# ATX_Power_Breakout_v1p5.net
KiCad netlist of a schematic drawn in EAGLE
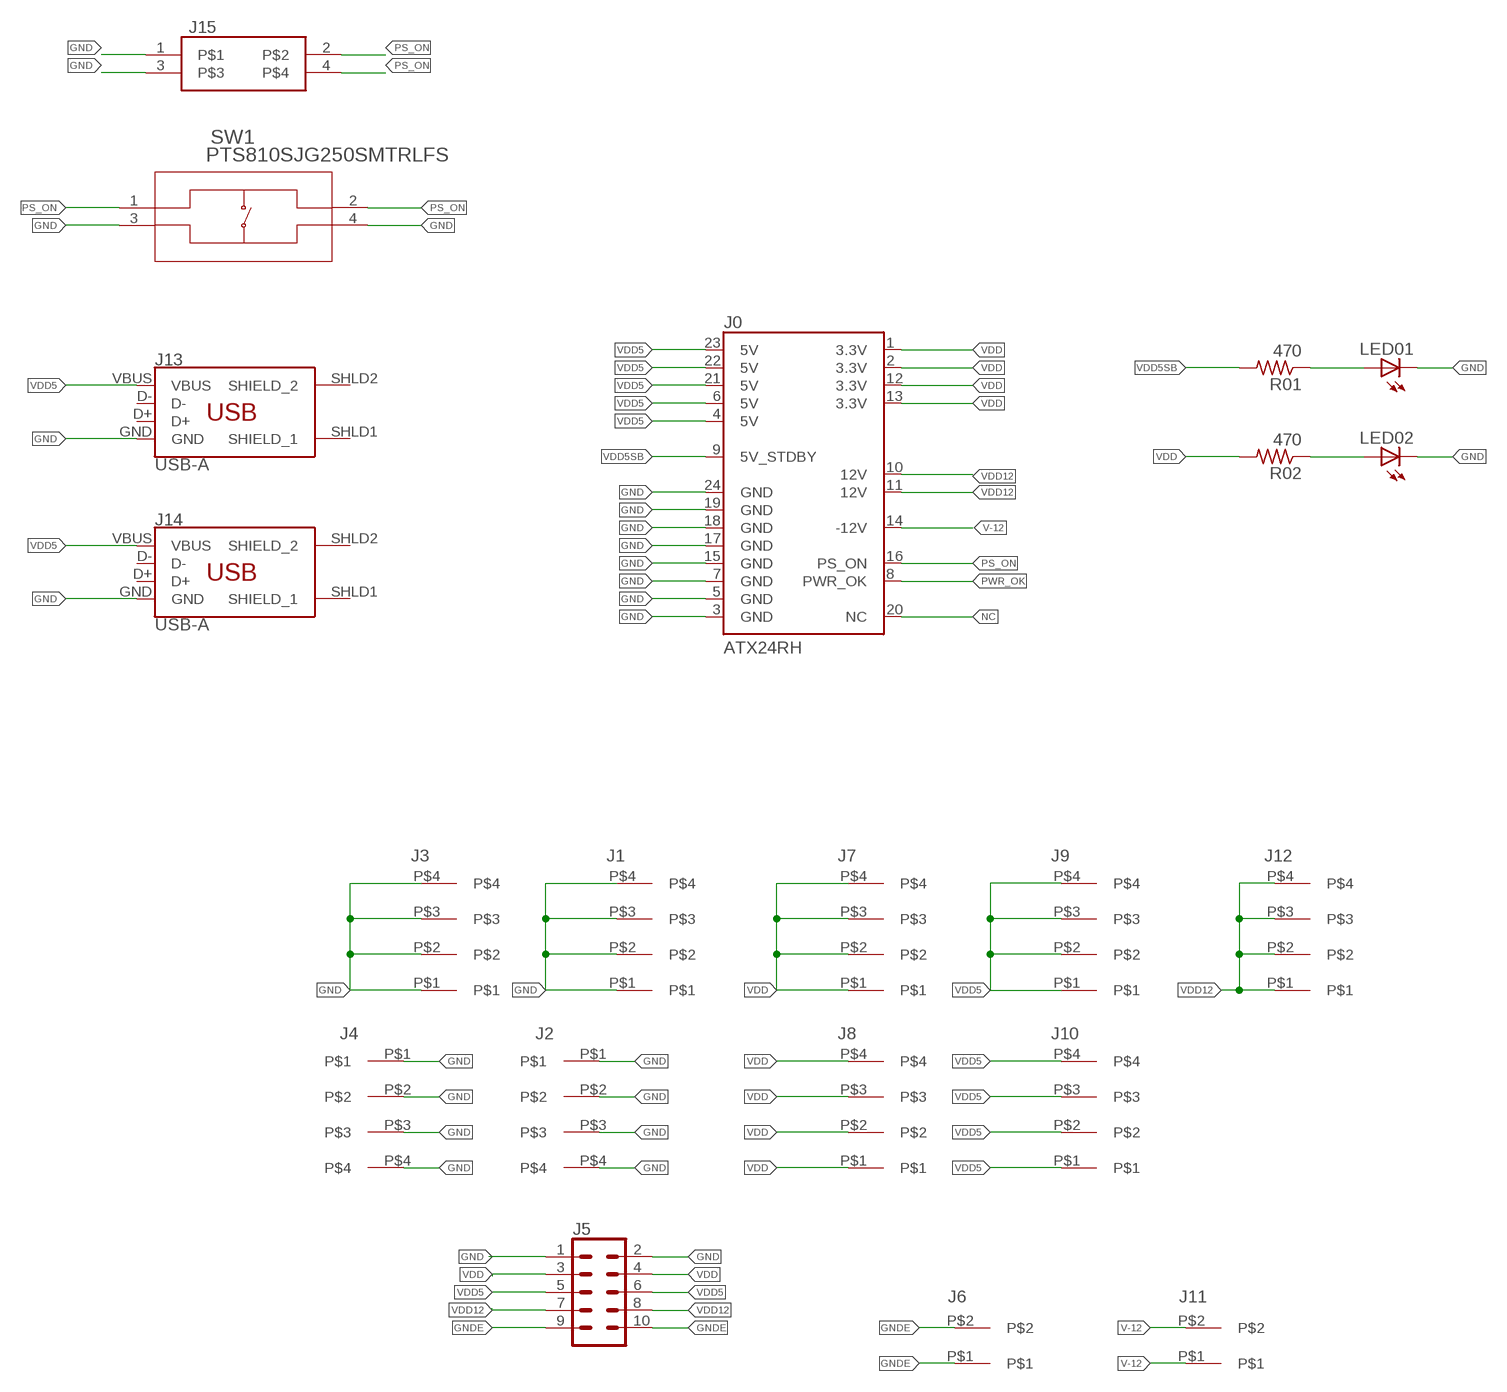
[diagram p0: schematic, sheet 1]

(export (version "E")
  (design (tool "Eeschema 10.0.6"))
  (components
    (comp (ref "J0")
      (value "ATX24RH")
      (footprint "eagle-import:ATX24_RIGHT_ANGLE")
      (libsource (lib "eagle-import") (part "ATX24RH"))
    )
    (comp (ref "J1")
      (value "3.81MM_1_X_4_RT_ANGLE_PLUG_HEADER")
      (footprint "eagle-import:1X4_3.81MM_PITCH")
      (libsource (lib "eagle-import") (part "3.81MM_1_X_4_RT_ANGLE_PLUG_HEADER"))
    )
    (comp (ref "J2")
      (value "3.81MM_1_X_4_RT_ANGLE_PLUG_HEADER")
      (footprint "eagle-import:1X4_3.81MM_PITCH")
      (libsource (lib "eagle-import") (part "3.81MM_1_X_4_RT_ANGLE_PLUG_HEADER"))
    )
    (comp (ref "J3")
      (value "3.81MM_1_X_4_RT_ANGLE_PLUG_HEADER")
      (footprint "eagle-import:1X4_3.81MM_PITCH")
      (libsource (lib "eagle-import") (part "3.81MM_1_X_4_RT_ANGLE_PLUG_HEADER"))
    )
    (comp (ref "J4")
      (value "3.81MM_1_X_4_RT_ANGLE_PLUG_HEADER")
      (footprint "eagle-import:1X4_3.81MM_PITCH")
      (libsource (lib "eagle-import") (part "3.81MM_1_X_4_RT_ANGLE_PLUG_HEADER"))
    )
    (comp (ref "J5")
      (value "CONN_05X2PTH")
      (footprint "eagle-import:2X5")
      (libsource (lib "eagle-import") (part "CONN_05X2PTH"))
    )
    (comp (ref "J6")
      (value "3.81MM_1_X_2_RT_ANGLE_PLUG_HEADER")
      (footprint "eagle-import:2_3.81MM_PITCH")
      (libsource (lib "eagle-import") (part "3.81MM_1_X_2_RT_ANGLE_PLUG_HEADER"))
    )
    (comp (ref "J7")
      (value "3.81MM_1_X_4_RT_ANGLE_PLUG_HEADER")
      (footprint "eagle-import:1X4_3.81MM_PITCH")
      (libsource (lib "eagle-import") (part "3.81MM_1_X_4_RT_ANGLE_PLUG_HEADER"))
    )
    (comp (ref "J8")
      (value "3.81MM_1_X_4_RT_ANGLE_PLUG_HEADER")
      (footprint "eagle-import:1X4_3.81MM_PITCH")
      (libsource (lib "eagle-import") (part "3.81MM_1_X_4_RT_ANGLE_PLUG_HEADER"))
    )
    (comp (ref "J9")
      (value "3.81MM_1_X_4_RT_ANGLE_PLUG_HEADER")
      (footprint "eagle-import:1X4_3.81MM_PITCH")
      (libsource (lib "eagle-import") (part "3.81MM_1_X_4_RT_ANGLE_PLUG_HEADER"))
    )
    (comp (ref "J10")
      (value "3.81MM_1_X_4_RT_ANGLE_PLUG_HEADER")
      (footprint "eagle-import:1X4_3.81MM_PITCH")
      (libsource (lib "eagle-import") (part "3.81MM_1_X_4_RT_ANGLE_PLUG_HEADER"))
    )
    (comp (ref "J11")
      (value "3.81MM_1_X_2_RT_ANGLE_PLUG_HEADER")
      (footprint "eagle-import:2_3.81MM_PITCH")
      (libsource (lib "eagle-import") (part "3.81MM_1_X_2_RT_ANGLE_PLUG_HEADER"))
    )
    (comp (ref "J12")
      (value "3.81MM_1_X_4_RT_ANGLE_PLUG_HEADER")
      (footprint "eagle-import:1X4_3.81MM_PITCH")
      (libsource (lib "eagle-import") (part "3.81MM_1_X_4_RT_ANGLE_PLUG_HEADER"))
    )
    (comp (ref "J13")
      (value "USB-A")
      (footprint "eagle-import:USB_A_SMT")
      (fields (field (name "PARTNO") "87583-3010RPALF"))
      (libsource (lib "eagle-import") (part "USB_A"))
    )
    (comp (ref "J14")
      (value "USB-A")
      (footprint "eagle-import:USB_A_SMT")
      (fields (field (name "PARTNO") "87583-3010RPALF"))
      (libsource (lib "eagle-import") (part "USB_A"))
    )
    (comp (ref "J15")
      (value "2.54MM_2_X_2_HEADER_GENERIC")
      (footprint "eagle-import:2X2")
      (libsource (lib "eagle-import") (part "2.54MM_2_X_2_HEADER_GENERIC"))
    )
    (comp (ref "LED01")
      (value "GREEN")
      (footprint "eagle-import:LED_0805_GREEN")
      (libsource (lib "eagle-import") (part "LED_0805_GREEN"))
    )
    (comp (ref "LED02")
      (value "GREEN")
      (footprint "eagle-import:LED_0805_GREEN")
      (libsource (lib "eagle-import") (part "LED_0805_GREEN"))
    )
    (comp (ref "R01")
      (value "470")
      (footprint "eagle-import:0402")
      (libsource (lib "eagle-import") (part "R_0402"))
    )
    (comp (ref "R02")
      (value "470")
      (footprint "eagle-import:0402")
      (libsource (lib "eagle-import") (part "R_0402"))
    )
    (comp (ref "SW1")
      (value "PTS810SJG250SMTRLFS")
      (footprint "eagle-import:PTS810")
      (fields (field (name "COPYRIGHT") "Copyright (C) 2018 Accelerated Designs. All rights reserved"))
      (libsource (lib "eagle-import") (part "PTS810SJG250SMTRLFS"))
    )
  )
  (nets
    (net (code "1") (name "GND") (class "Default")
      (node (ref "J0") (pin "15") (pinfunction "GND_15") (pintype "bidirectional"))
      (node (ref "J0") (pin "17") (pinfunction "GND_17") (pintype "bidirectional"))
      (node (ref "J0") (pin "18") (pinfunction "GND_18") (pintype "bidirectional"))
      (node (ref "J0") (pin "19") (pinfunction "GND_19") (pintype "bidirectional"))
      (node (ref "J0") (pin "24") (pinfunction "GND_24") (pintype "bidirectional"))
      (node (ref "J0") (pin "3") (pinfunction "GND_3") (pintype "bidirectional"))
      (node (ref "J0") (pin "5") (pinfunction "GND_5") (pintype "bidirectional"))
      (node (ref "J0") (pin "7") (pinfunction "GND_7") (pintype "bidirectional"))
      (node (ref "J1") (pin "P$1") (pinfunction "P$1_P$1") (pintype "bidirectional"))
      (node (ref "J1") (pin "P$2") (pinfunction "P$2_P$2") (pintype "bidirectional"))
      (node (ref "J1") (pin "P$3") (pinfunction "P$3_P$3") (pintype "bidirectional"))
      (node (ref "J1") (pin "P$4") (pinfunction "P$4_P$4") (pintype "bidirectional"))
      (node (ref "J13") (pin "GND") (pinfunction "GND_GND") (pintype "power_in"))
      (node (ref "J14") (pin "GND") (pinfunction "GND_GND") (pintype "power_in"))
      (node (ref "J15") (pin "1") (pinfunction "P$1_1") (pintype "bidirectional"))
      (node (ref "J15") (pin "3") (pinfunction "P$3_3") (pintype "bidirectional"))
      (node (ref "J2") (pin "P$1") (pinfunction "P$1_P$1") (pintype "bidirectional"))
      (node (ref "J2") (pin "P$2") (pinfunction "P$2_P$2") (pintype "bidirectional"))
      (node (ref "J2") (pin "P$3") (pinfunction "P$3_P$3") (pintype "bidirectional"))
      (node (ref "J2") (pin "P$4") (pinfunction "P$4_P$4") (pintype "bidirectional"))
      (node (ref "J3") (pin "P$1") (pinfunction "P$1_P$1") (pintype "bidirectional"))
      (node (ref "J3") (pin "P$2") (pinfunction "P$2_P$2") (pintype "bidirectional"))
      (node (ref "J3") (pin "P$3") (pinfunction "P$3_P$3") (pintype "bidirectional"))
      (node (ref "J3") (pin "P$4") (pinfunction "P$4_P$4") (pintype "bidirectional"))
      (node (ref "J4") (pin "P$1") (pinfunction "P$1_P$1") (pintype "bidirectional"))
      (node (ref "J4") (pin "P$2") (pinfunction "P$2_P$2") (pintype "bidirectional"))
      (node (ref "J4") (pin "P$3") (pinfunction "P$3_P$3") (pintype "bidirectional"))
      (node (ref "J4") (pin "P$4") (pinfunction "P$4_P$4") (pintype "bidirectional"))
      (node (ref "J5") (pin "1") (pinfunction "1_1") (pintype "passive"))
      (node (ref "J5") (pin "2") (pinfunction "2_2") (pintype "passive"))
      (node (ref "LED01") (pin "C") (pinfunction "C_C") (pintype "passive"))
      (node (ref "LED02") (pin "C") (pinfunction "C_C") (pintype "passive"))
      (node (ref "SW1") (pin "3") (pinfunction "3_3") (pintype "passive"))
      (node (ref "SW1") (pin "4") (pinfunction "4_4") (pintype "passive"))
    )
    (net (code "2") (name "GNDE") (class "Default")
      (node (ref "J5") (pin "10") (pinfunction "10_10") (pintype "passive"))
      (node (ref "J5") (pin "9") (pinfunction "9_9") (pintype "passive"))
      (node (ref "J6") (pin "P$1") (pinfunction "P$1_P$1") (pintype "bidirectional"))
      (node (ref "J6") (pin "P$2") (pinfunction "P$2_P$2") (pintype "bidirectional"))
    )
    (net (code "3") (name "NC") (class "Default")
      (node (ref "J0") (pin "20") (pinfunction "NC_20") (pintype "bidirectional"))
    )
    (net (code "4") (name "Net-(R01-1)") (class "Default")
      (node (ref "LED01") (pin "A") (pinfunction "A_A") (pintype "passive"))
      (node (ref "R01") (pin "P$1") (pinfunction "1_P$1") (pintype "passive"))
    )
    (net (code "5") (name "Net-(R02-1)") (class "Default")
      (node (ref "LED02") (pin "A") (pinfunction "A_A") (pintype "passive"))
      (node (ref "R02") (pin "P$1") (pinfunction "1_P$1") (pintype "passive"))
    )
    (net (code "6") (name "PS_ON") (class "Default")
      (node (ref "J0") (pin "16") (pinfunction "PS_ON_16") (pintype "bidirectional"))
      (node (ref "J15") (pin "2") (pinfunction "P$2_2") (pintype "bidirectional"))
      (node (ref "J15") (pin "4") (pinfunction "P$4_4") (pintype "bidirectional"))
      (node (ref "SW1") (pin "1") (pinfunction "1_1") (pintype "passive"))
      (node (ref "SW1") (pin "2") (pinfunction "2_2") (pintype "passive"))
    )
    (net (code "7") (name "PWR_OK") (class "Default")
      (node (ref "J0") (pin "8") (pinfunction "PWR_OK_8") (pintype "bidirectional"))
    )
    (net (code "8") (name "V-12") (class "Default")
      (node (ref "J0") (pin "14") (pinfunction "-12V_14") (pintype "bidirectional"))
      (node (ref "J11") (pin "P$1") (pinfunction "P$1_P$1") (pintype "bidirectional"))
      (node (ref "J11") (pin "P$2") (pinfunction "P$2_P$2") (pintype "bidirectional"))
    )
    (net (code "9") (name "VDD") (class "Default")
      (node (ref "J0") (pin "1") (pinfunction "3.3V_1") (pintype "bidirectional"))
      (node (ref "J0") (pin "12") (pinfunction "3.3V_12") (pintype "bidirectional"))
      (node (ref "J0") (pin "13") (pinfunction "3.3V_13") (pintype "bidirectional"))
      (node (ref "J0") (pin "2") (pinfunction "3.3V_2") (pintype "bidirectional"))
      (node (ref "J5") (pin "3") (pinfunction "3_3") (pintype "passive"))
      (node (ref "J5") (pin "4") (pinfunction "4_4") (pintype "passive"))
      (node (ref "J7") (pin "P$1") (pinfunction "P$1_P$1") (pintype "bidirectional"))
      (node (ref "J7") (pin "P$2") (pinfunction "P$2_P$2") (pintype "bidirectional"))
      (node (ref "J7") (pin "P$3") (pinfunction "P$3_P$3") (pintype "bidirectional"))
      (node (ref "J7") (pin "P$4") (pinfunction "P$4_P$4") (pintype "bidirectional"))
      (node (ref "J8") (pin "P$1") (pinfunction "P$1_P$1") (pintype "bidirectional"))
      (node (ref "J8") (pin "P$2") (pinfunction "P$2_P$2") (pintype "bidirectional"))
      (node (ref "J8") (pin "P$3") (pinfunction "P$3_P$3") (pintype "bidirectional"))
      (node (ref "J8") (pin "P$4") (pinfunction "P$4_P$4") (pintype "bidirectional"))
      (node (ref "R02") (pin "P$2") (pinfunction "2_P$2") (pintype "passive"))
    )
    (net (code "10") (name "VDD5") (class "Default")
      (node (ref "J0") (pin "21") (pinfunction "5V_21") (pintype "bidirectional"))
      (node (ref "J0") (pin "22") (pinfunction "5V_22") (pintype "bidirectional"))
      (node (ref "J0") (pin "23") (pinfunction "5V_23") (pintype "bidirectional"))
      (node (ref "J0") (pin "4") (pinfunction "5V_4") (pintype "bidirectional"))
      (node (ref "J0") (pin "6") (pinfunction "5V_6") (pintype "bidirectional"))
      (node (ref "J10") (pin "P$1") (pinfunction "P$1_P$1") (pintype "bidirectional"))
      (node (ref "J10") (pin "P$2") (pinfunction "P$2_P$2") (pintype "bidirectional"))
      (node (ref "J10") (pin "P$3") (pinfunction "P$3_P$3") (pintype "bidirectional"))
      (node (ref "J10") (pin "P$4") (pinfunction "P$4_P$4") (pintype "bidirectional"))
      (node (ref "J13") (pin "VBUS") (pinfunction "VBUS_VBUS") (pintype "power_in"))
      (node (ref "J14") (pin "VBUS") (pinfunction "VBUS_VBUS") (pintype "power_in"))
      (node (ref "J5") (pin "5") (pinfunction "5_5") (pintype "passive"))
      (node (ref "J5") (pin "6") (pinfunction "6_6") (pintype "passive"))
      (node (ref "J9") (pin "P$1") (pinfunction "P$1_P$1") (pintype "bidirectional"))
      (node (ref "J9") (pin "P$2") (pinfunction "P$2_P$2") (pintype "bidirectional"))
      (node (ref "J9") (pin "P$3") (pinfunction "P$3_P$3") (pintype "bidirectional"))
      (node (ref "J9") (pin "P$4") (pinfunction "P$4_P$4") (pintype "bidirectional"))
    )
    (net (code "11") (name "VDD5SB") (class "Default")
      (node (ref "J0") (pin "9") (pinfunction "5V_STDBY_9") (pintype "bidirectional"))
      (node (ref "R01") (pin "P$2") (pinfunction "2_P$2") (pintype "passive"))
    )
    (net (code "12") (name "VDD12") (class "Default")
      (node (ref "J0") (pin "10") (pinfunction "12V_10") (pintype "bidirectional"))
      (node (ref "J0") (pin "11") (pinfunction "12V_11") (pintype "bidirectional"))
      (node (ref "J12") (pin "P$1") (pinfunction "P$1_P$1") (pintype "bidirectional"))
      (node (ref "J12") (pin "P$2") (pinfunction "P$2_P$2") (pintype "bidirectional"))
      (node (ref "J12") (pin "P$3") (pinfunction "P$3_P$3") (pintype "bidirectional"))
      (node (ref "J12") (pin "P$4") (pinfunction "P$4_P$4") (pintype "bidirectional"))
      (node (ref "J5") (pin "7") (pinfunction "7_7") (pintype "passive"))
      (node (ref "J5") (pin "8") (pinfunction "8_8") (pintype "passive"))
    )
    (net (code "13") (name "unconnected-(J13-PadD+)") (class "Default")
      (node (ref "J13") (pin "D+") (pinfunction "D+_D+") (pintype "bidirectional"))
    )
    (net (code "14") (name "unconnected-(J13-PadD-)") (class "Default")
      (node (ref "J13") (pin "D-") (pinfunction "D-_D-") (pintype "bidirectional"))
    )
    (net (code "15") (name "unconnected-(J13-SHIELD_1-PadSHLD1)") (class "Default")
      (node (ref "J13") (pin "SHLD1") (pinfunction "SHIELD_1_SHLD1") (pintype "bidirectional"))
    )
    (net (code "16") (name "unconnected-(J13-SHIELD_2-PadSHLD2)") (class "Default")
      (node (ref "J13") (pin "SHLD2") (pinfunction "SHIELD_2_SHLD2") (pintype "bidirectional"))
    )
    (net (code "17") (name "unconnected-(J14-PadD+)") (class "Default")
      (node (ref "J14") (pin "D+") (pinfunction "D+_D+") (pintype "bidirectional"))
    )
    (net (code "18") (name "unconnected-(J14-PadD-)") (class "Default")
      (node (ref "J14") (pin "D-") (pinfunction "D-_D-") (pintype "bidirectional"))
    )
    (net (code "19") (name "unconnected-(J14-SHIELD_1-PadSHLD1)") (class "Default")
      (node (ref "J14") (pin "SHLD1") (pinfunction "SHIELD_1_SHLD1") (pintype "bidirectional"))
    )
    (net (code "20") (name "unconnected-(J14-SHIELD_2-PadSHLD2)") (class "Default")
      (node (ref "J14") (pin "SHLD2") (pinfunction "SHIELD_2_SHLD2") (pintype "bidirectional"))
    )
  )
)
